# 51MCU.net
KiCad netlist of a schematic drawn in Altium Designer
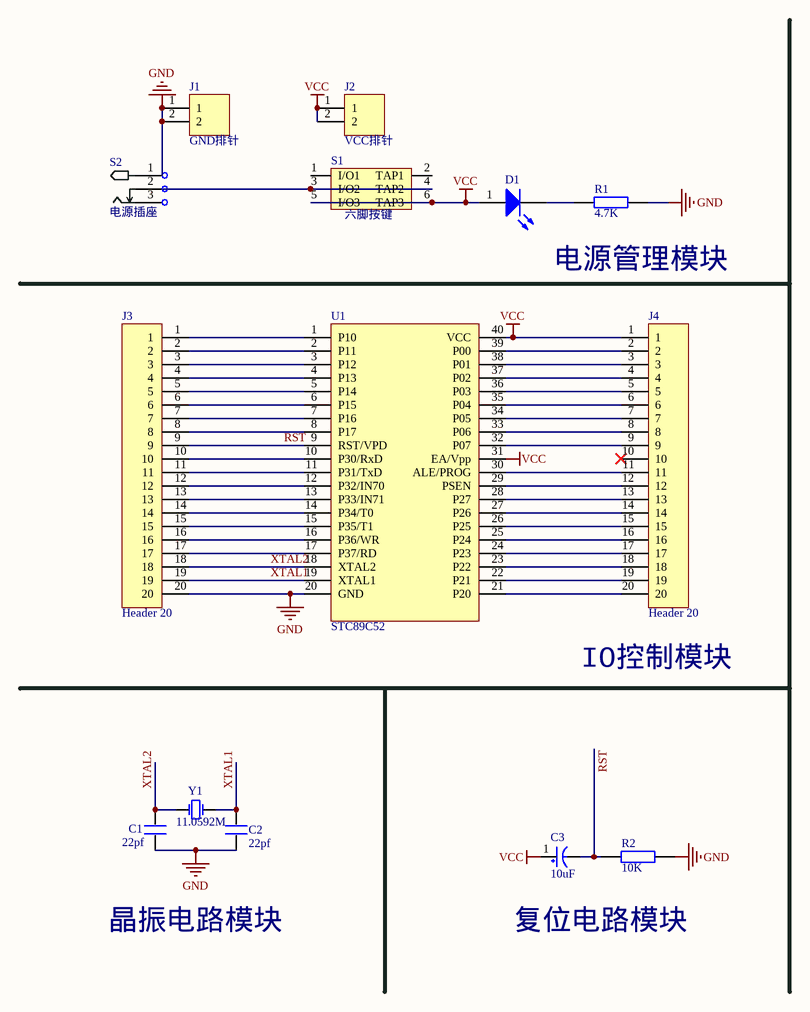
[diagram p0: 51MCU最小系统.SchDoc]

(export (version "E")
  (design (tool "Eeschema 10.0.6"))
  (components
    (comp (ref "C1")
      (value "22pf")
      (footprint "MyPcbLib:CAP_2.54_NO_ele")
      (libsource (lib "MySchLib") (part "C-dip"))
    )
    (comp (ref "C2")
      (value "22pf")
      (footprint "MyPcbLib:CAP_2.54_NO_ele")
      (libsource (lib "MySchLib") (part "C-dip"))
    )
    (comp (ref "C3")
      (value "10uF")
      (footprint "MyPcbLib:Cap_3.0")
      (libsource (lib "MySchLib") (part "C-ele"))
    )
    (comp (ref "D1")
      (value "LED-Diode-DIP")
      (footprint "MyPcbLib:LED_DIP")
      (libsource (lib "MySchLib") (part "LED-Diode-DIP"))
    )
    (comp (ref "J1")
      (value "GND排针")
      (footprint "MyPcbLib:Header 2")
      (libsource (lib "MySchLib") (part "Header 2"))
    )
    (comp (ref "J2")
      (value "VCC排针")
      (footprint "MyPcbLib:Header 2")
      (libsource (lib "MySchLib") (part "Header 2"))
    )
    (comp (ref "J3")
      (value "Header 20")
      (footprint "MyPcbLib:Header 20")
      (libsource (lib "") (part "Header 20_1"))
    )
    (comp (ref "J4")
      (value "Header 20")
      (footprint "MyPcbLib:Header 20")
      (libsource (lib "MySchLib") (part "Header 20"))
    )
    (comp (ref "R1")
      (value "4.7K")
      (footprint "MyPcbLib:Res-dip - duplicate")
      (libsource (lib "") (part "Res-DIP_1"))
    )
    (comp (ref "R2")
      (value "10K")
      (footprint "MyPcbLib:Res-dip - duplicate")
      (libsource (lib "MySchLib") (part "Res-DIP"))
    )
    (comp (ref "S1") (value "六脚按键") (footprint "MyPcbLib:Key-6") (libsource (lib "MySchLib") (part "KEY-6")))
    (comp (ref "S2")
      (value "电源插座")
      (footprint "MyPcbLib:DC-005")
      (libsource (lib "MySchLib") (part "DC-005"))
    )
    (comp (ref "U1")
      (value "STC89C52")
      (footprint "MyPcbLib:DIP-40")
      (libsource (lib "MySchLib") (part "STC89C52"))
    )
    (comp (ref "Y1")
      (value "11.0592M")
      (footprint "MyPcbLib:XTAL_SOP")
      (libsource (lib "MySchLib") (part "XTAL"))
    )
  )
  (nets
    (net (code "1") (name "/RST") (class "Default")
      (node (ref "C3") (pin "2") (pinfunction "GND_2") (pintype "passive"))
      (node (ref "J3") (pin "9") (pinfunction "9_9") (pintype "passive"))
      (node (ref "R2") (pin "2") (pinfunction "2_2") (pintype "passive"))
      (node (ref "U1") (pin "9") (pinfunction "RST/VPD_9") (pintype "passive"))
    )
    (net (code "2") (name "/XTAL1") (class "Default")
      (node (ref "C2") (pin "1") (pintype "passive"))
      (node (ref "J3") (pin "19") (pinfunction "19_19") (pintype "passive"))
      (node (ref "U1") (pin "19") (pinfunction "XTAL1_19") (pintype "passive"))
      (node (ref "Y1") (pin "1") (pinfunction "OSC1_1") (pintype "passive"))
    )
    (net (code "3") (name "/XTAL2") (class "Default")
      (node (ref "C1") (pin "1") (pintype "passive"))
      (node (ref "J3") (pin "18") (pinfunction "18_18") (pintype "passive"))
      (node (ref "U1") (pin "18") (pinfunction "XTAL2_18") (pintype "passive"))
      (node (ref "Y1") (pin "2") (pinfunction "OSC2_2") (pintype "passive"))
    )
    (net (code "4") (name "GND") (class "Default")
      (node (ref "C1") (pin "2") (pintype "passive"))
      (node (ref "C2") (pin "2") (pintype "passive"))
      (node (ref "J1") (pin "1") (pinfunction "1_1") (pintype "passive"))
      (node (ref "J1") (pin "2") (pinfunction "2_2") (pintype "passive"))
      (node (ref "J3") (pin "20") (pinfunction "20_20") (pintype "passive"))
      (node (ref "R1") (pin "2") (pinfunction "2_2") (pintype "passive"))
      (node (ref "R2") (pin "1") (pinfunction "1_1") (pintype "passive"))
      (node (ref "S2") (pin "1") (pinfunction "1_1") (pintype "passive"))
      (node (ref "U1") (pin "20") (pinfunction "GND_20") (pintype "passive"))
    )
    (net (code "5") (name "Net-(D1-K)") (class "Default")
      (node (ref "D1") (pin "2") (pinfunction "K_2") (pintype "passive"))
      (node (ref "R1") (pin "1") (pinfunction "1_1") (pintype "passive"))
    )
    (net (code "6") (name "Net-(S1-I{slash}O2)") (class "Default")
      (node (ref "S1") (pin "3") (pinfunction "I/O2_3") (pintype "passive"))
      (node (ref "S1") (pin "4") (pinfunction "TAP2_4") (pintype "passive"))
      (node (ref "S2") (pin "2") (pinfunction "2_2") (pintype "passive"))
    )
    (net (code "7") (name "Net-(U1-ALE{slash}PROG)") (class "Default")
      (node (ref "J4") (pin "11") (pinfunction "11_11") (pintype "passive"))
      (node (ref "U1") (pin "30") (pinfunction "ALE/PROG_30") (pintype "passive"))
    )
    (net (code "8") (name "Net-(U1-P00)") (class "Default")
      (node (ref "J4") (pin "2") (pinfunction "2_2") (pintype "passive"))
      (node (ref "U1") (pin "39") (pinfunction "P00_39") (pintype "passive"))
    )
    (net (code "9") (name "Net-(U1-P01)") (class "Default")
      (node (ref "J4") (pin "3") (pinfunction "3_3") (pintype "passive"))
      (node (ref "U1") (pin "38") (pinfunction "P01_38") (pintype "passive"))
    )
    (net (code "10") (name "Net-(U1-P02)") (class "Default")
      (node (ref "J4") (pin "4") (pinfunction "4_4") (pintype "passive"))
      (node (ref "U1") (pin "37") (pinfunction "P02_37") (pintype "passive"))
    )
    (net (code "11") (name "Net-(U1-P03)") (class "Default")
      (node (ref "J4") (pin "5") (pinfunction "5_5") (pintype "passive"))
      (node (ref "U1") (pin "36") (pinfunction "P03_36") (pintype "passive"))
    )
    (net (code "12") (name "Net-(U1-P04)") (class "Default")
      (node (ref "J4") (pin "6") (pinfunction "6_6") (pintype "passive"))
      (node (ref "U1") (pin "35") (pinfunction "P04_35") (pintype "passive"))
    )
    (net (code "13") (name "Net-(U1-P05)") (class "Default")
      (node (ref "J4") (pin "7") (pinfunction "7_7") (pintype "passive"))
      (node (ref "U1") (pin "34") (pinfunction "P05_34") (pintype "passive"))
    )
    (net (code "14") (name "Net-(U1-P06)") (class "Default")
      (node (ref "J4") (pin "8") (pinfunction "8_8") (pintype "passive"))
      (node (ref "U1") (pin "33") (pinfunction "P06_33") (pintype "passive"))
    )
    (net (code "15") (name "Net-(U1-P07)") (class "Default")
      (node (ref "J4") (pin "9") (pinfunction "9_9") (pintype "passive"))
      (node (ref "U1") (pin "32") (pinfunction "P07_32") (pintype "passive"))
    )
    (net (code "16") (name "Net-(U1-P10)") (class "Default")
      (node (ref "J3") (pin "1") (pinfunction "1_1") (pintype "passive"))
      (node (ref "U1") (pin "1") (pinfunction "P10_1") (pintype "passive"))
    )
    (net (code "17") (name "Net-(U1-P11)") (class "Default")
      (node (ref "J3") (pin "2") (pinfunction "2_2") (pintype "passive"))
      (node (ref "U1") (pin "2") (pinfunction "P11_2") (pintype "passive"))
    )
    (net (code "18") (name "Net-(U1-P12)") (class "Default")
      (node (ref "J3") (pin "3") (pinfunction "3_3") (pintype "passive"))
      (node (ref "U1") (pin "3") (pinfunction "P12_3") (pintype "passive"))
    )
    (net (code "19") (name "Net-(U1-P13)") (class "Default")
      (node (ref "J3") (pin "4") (pinfunction "4_4") (pintype "passive"))
      (node (ref "U1") (pin "4") (pinfunction "P13_4") (pintype "passive"))
    )
    (net (code "20") (name "Net-(U1-P14)") (class "Default")
      (node (ref "J3") (pin "5") (pinfunction "5_5") (pintype "passive"))
      (node (ref "U1") (pin "5") (pinfunction "P14_5") (pintype "passive"))
    )
    (net (code "21") (name "Net-(U1-P15)") (class "Default")
      (node (ref "J3") (pin "6") (pinfunction "6_6") (pintype "passive"))
      (node (ref "U1") (pin "6") (pinfunction "P15_6") (pintype "passive"))
    )
    (net (code "22") (name "Net-(U1-P16)") (class "Default")
      (node (ref "J3") (pin "7") (pinfunction "7_7") (pintype "passive"))
      (node (ref "U1") (pin "7") (pinfunction "P16_7") (pintype "passive"))
    )
    (net (code "23") (name "Net-(U1-P17)") (class "Default")
      (node (ref "J3") (pin "8") (pinfunction "8_8") (pintype "passive"))
      (node (ref "U1") (pin "8") (pinfunction "P17_8") (pintype "passive"))
    )
    (net (code "24") (name "Net-(U1-P20)") (class "Default")
      (node (ref "J4") (pin "20") (pinfunction "20_20") (pintype "passive"))
      (node (ref "U1") (pin "21") (pinfunction "P20_21") (pintype "passive"))
    )
    (net (code "25") (name "Net-(U1-P21)") (class "Default")
      (node (ref "J4") (pin "19") (pinfunction "19_19") (pintype "passive"))
      (node (ref "U1") (pin "22") (pinfunction "P21_22") (pintype "passive"))
    )
    (net (code "26") (name "Net-(U1-P22)") (class "Default")
      (node (ref "J4") (pin "18") (pinfunction "18_18") (pintype "passive"))
      (node (ref "U1") (pin "23") (pinfunction "P22_23") (pintype "passive"))
    )
    (net (code "27") (name "Net-(U1-P23)") (class "Default")
      (node (ref "J4") (pin "17") (pinfunction "17_17") (pintype "passive"))
      (node (ref "U1") (pin "24") (pinfunction "P23_24") (pintype "passive"))
    )
    (net (code "28") (name "Net-(U1-P24)") (class "Default")
      (node (ref "J4") (pin "16") (pinfunction "16_16") (pintype "passive"))
      (node (ref "U1") (pin "25") (pinfunction "P24_25") (pintype "passive"))
    )
    (net (code "29") (name "Net-(U1-P25)") (class "Default")
      (node (ref "J4") (pin "15") (pinfunction "15_15") (pintype "passive"))
      (node (ref "U1") (pin "26") (pinfunction "P25_26") (pintype "passive"))
    )
    (net (code "30") (name "Net-(U1-P26)") (class "Default")
      (node (ref "J4") (pin "14") (pinfunction "14_14") (pintype "passive"))
      (node (ref "U1") (pin "27") (pinfunction "P26_27") (pintype "passive"))
    )
    (net (code "31") (name "Net-(U1-P27)") (class "Default")
      (node (ref "J4") (pin "13") (pinfunction "13_13") (pintype "passive"))
      (node (ref "U1") (pin "28") (pinfunction "P27_28") (pintype "passive"))
    )
    (net (code "32") (name "Net-(U1-P30{slash}RxD)") (class "Default")
      (node (ref "J3") (pin "10") (pinfunction "10_10") (pintype "passive"))
      (node (ref "U1") (pin "10") (pinfunction "P30/RxD_10") (pintype "passive"))
    )
    (net (code "33") (name "Net-(U1-P31{slash}TxD)") (class "Default")
      (node (ref "J3") (pin "11") (pinfunction "11_11") (pintype "passive"))
      (node (ref "U1") (pin "11") (pinfunction "P31/TxD_11") (pintype "passive"))
    )
    (net (code "34") (name "Net-(U1-P32{slash}IN70)") (class "Default")
      (node (ref "J3") (pin "12") (pinfunction "12_12") (pintype "passive"))
      (node (ref "U1") (pin "12") (pinfunction "P32/IN70_12") (pintype "passive"))
    )
    (net (code "35") (name "Net-(U1-P33{slash}IN71)") (class "Default")
      (node (ref "J3") (pin "13") (pinfunction "13_13") (pintype "passive"))
      (node (ref "U1") (pin "13") (pinfunction "P33/IN71_13") (pintype "passive"))
    )
    (net (code "36") (name "Net-(U1-P34{slash}T0)") (class "Default")
      (node (ref "J3") (pin "14") (pinfunction "14_14") (pintype "passive"))
      (node (ref "U1") (pin "14") (pinfunction "P34/T0_14") (pintype "passive"))
    )
    (net (code "37") (name "Net-(U1-P35{slash}T1)") (class "Default")
      (node (ref "J3") (pin "15") (pinfunction "15_15") (pintype "passive"))
      (node (ref "U1") (pin "15") (pinfunction "P35/T1_15") (pintype "passive"))
    )
    (net (code "38") (name "Net-(U1-P36{slash}WR)") (class "Default")
      (node (ref "J3") (pin "16") (pinfunction "16_16") (pintype "passive"))
      (node (ref "U1") (pin "16") (pinfunction "P36/WR_16") (pintype "passive"))
    )
    (net (code "39") (name "Net-(U1-P37{slash}RD)") (class "Default")
      (node (ref "J3") (pin "17") (pinfunction "17_17") (pintype "passive"))
      (node (ref "U1") (pin "17") (pinfunction "P37/RD_17") (pintype "passive"))
    )
    (net (code "40") (name "Net-(U1-PSEN)") (class "Default")
      (node (ref "J4") (pin "12") (pinfunction "12_12") (pintype "passive"))
      (node (ref "U1") (pin "29") (pinfunction "PSEN_29") (pintype "passive"))
    )
    (net (code "41") (name "VCC") (class "Default")
      (node (ref "C3") (pin "1") (pinfunction "VCC_1") (pintype "passive"))
      (node (ref "D1") (pin "1") (pinfunction "A_1") (pintype "passive"))
      (node (ref "J2") (pin "1") (pinfunction "1_1") (pintype "passive"))
      (node (ref "J2") (pin "2") (pinfunction "2_2") (pintype "passive"))
      (node (ref "J4") (pin "1") (pinfunction "1_1") (pintype "passive"))
      (node (ref "S1") (pin "5") (pinfunction "I/O3_5") (pintype "passive"))
      (node (ref "S1") (pin "6") (pinfunction "TAP3_6") (pintype "passive"))
      (node (ref "U1") (pin "31") (pinfunction "EA/Vpp_31") (pintype "passive"))
      (node (ref "U1") (pin "40") (pinfunction "VCC_40") (pintype "passive"))
    )
    (net (code "42") (name "unconnected-(J4-Pad10)") (class "Default")
      (node (ref "J4") (pin "10") (pinfunction "10_10") (pintype "passive+no_connect"))
    )
    (net (code "43") (name "unconnected-(S1-I{slash}O1-Pad1)") (class "Default")
      (node (ref "S1") (pin "1") (pinfunction "I/O1_1") (pintype "passive"))
    )
    (net (code "44") (name "unconnected-(S1-TAP1-Pad2)") (class "Default")
      (node (ref "S1") (pin "2") (pinfunction "TAP1_2") (pintype "passive"))
    )
    (net (code "45") (name "unconnected-(S2-Pad3)") (class "Default")
      (node (ref "S2") (pin "3") (pinfunction "3_3") (pintype "passive"))
    )
  )
)
